# YarnControl_Connect_v1_0.net
KiCad netlist of a schematic drawn in Altium Designer
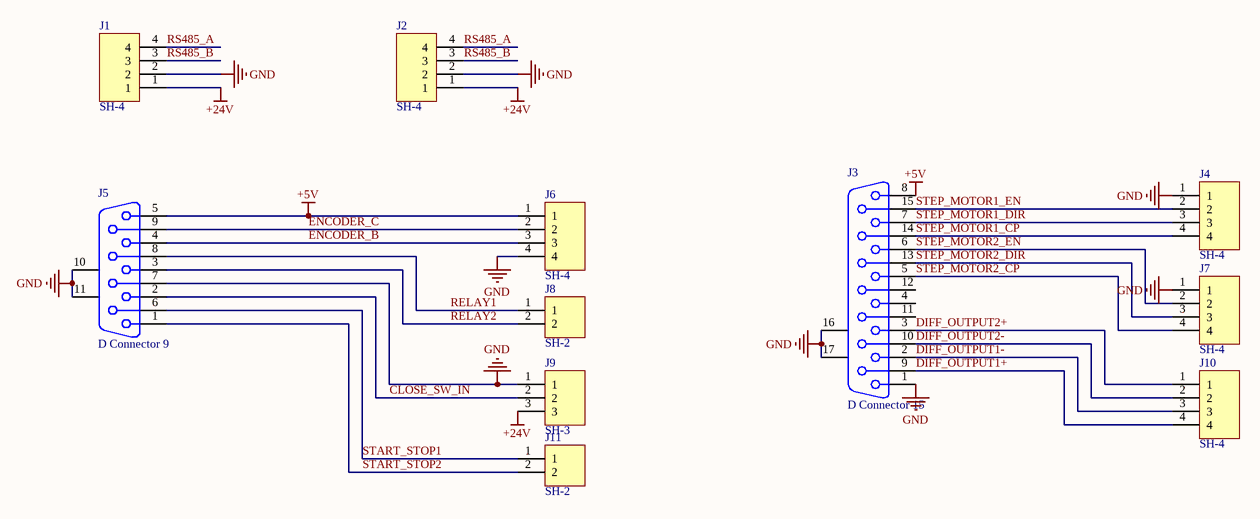
[diagram p0: YarnControl_Connect_v1.0.SchDoc]

(export (version "E")
  (design (tool "Eeschema 10.0.6"))
  (components
    (comp (ref "J1") (value "SH-4") (footprint "PWR") (libsource (lib "") (part "SH-4_1")))
    (comp (ref "J2") (value "SH-4") (footprint "PWR") (libsource (lib "") (part "SH-4_1")))
    (comp (ref "J3")
      (value "D Connector 15")
      (footprint "DSUB1.385-2H15")
      (description "Receptacle Assembly, 15 Position, Right Angle")
      (fields (field (name "PUBLISHER") "Altium Limited"))
      (libsource (lib "Miscellaneous Connectors") (part "D Connector 15"))
    )
    (comp (ref "J4") (value "SH-4") (footprint "PWR") (libsource (lib "Connector") (part "SH-4")))
    (comp (ref "J5")
      (value "D Connector 9")
      (footprint "DSUB1.385-2H9")
      (description "Receptacle Assembly, 9 Position, Right Angle")
      (fields (field (name "PUBLISHER") "Altium Limited"))
      (libsource (lib "Miscellaneous Connectors") (part "D Connector 9"))
    )
    (comp (ref "J6") (value "SH-4") (footprint "PWR") (libsource (lib "Connector") (part "SH-4")))
    (comp (ref "J7") (value "SH-4") (footprint "PWR") (libsource (lib "Connector") (part "SH-4")))
    (comp (ref "J8") (value "SH-2") (footprint "J508-2(1)") (libsource (lib "Connector") (part "SH-2")))
    (comp (ref "J9") (value "SH-3") (footprint "J508-3") (libsource (lib "Connector") (part "SH-3")))
    (comp (ref "J10") (value "SH-4") (footprint "PWR") (libsource (lib "Connector") (part "SH-4")))
    (comp (ref "J11") (value "SH-2") (footprint "J508-2(1)") (libsource (lib "Connector") (part "SH-2")))
  )
  (nets
    (net (code "1") (name "+5V") (class "Default")
      (node (ref "J3") (pin "8") (pinfunction "8_8") (pintype "passive"))
      (node (ref "J5") (pin "5") (pinfunction "5_5") (pintype "passive"))
      (node (ref "J6") (pin "1") (pinfunction "1_1") (pintype "passive"))
    )
    (net (code "2") (name "+24V") (class "Default")
      (node (ref "J1") (pin "1") (pinfunction "1_1") (pintype "passive"))
      (node (ref "J2") (pin "1") (pinfunction "1_1") (pintype "passive"))
      (node (ref "J9") (pin "3") (pinfunction "3_3") (pintype "passive"))
    )
    (net (code "3") (name "/CLOSE_SW_IN") (class "Default")
      (node (ref "J5") (pin "2") (pinfunction "2_2") (pintype "passive"))
      (node (ref "J9") (pin "2") (pinfunction "2_2") (pintype "passive"))
    )
    (net (code "4") (name "/DIFF_OUTPUT1+") (class "Default")
      (node (ref "J10") (pin "4") (pinfunction "4_4") (pintype "passive"))
      (node (ref "J3") (pin "9") (pinfunction "9_9") (pintype "passive"))
    )
    (net (code "5") (name "/DIFF_OUTPUT1-") (class "Default")
      (node (ref "J10") (pin "3") (pinfunction "3_3") (pintype "passive"))
      (node (ref "J3") (pin "2") (pinfunction "2_2") (pintype "passive"))
    )
    (net (code "6") (name "/DIFF_OUTPUT2+") (class "Default")
      (node (ref "J10") (pin "1") (pinfunction "1_1") (pintype "passive"))
      (node (ref "J3") (pin "3") (pinfunction "3_3") (pintype "passive"))
    )
    (net (code "7") (name "/DIFF_OUTPUT2-") (class "Default")
      (node (ref "J10") (pin "2") (pinfunction "2_2") (pintype "passive"))
      (node (ref "J3") (pin "10") (pinfunction "10_10") (pintype "passive"))
    )
    (net (code "8") (name "/ENCODER_B") (class "Default")
      (node (ref "J5") (pin "4") (pinfunction "4_4") (pintype "passive"))
      (node (ref "J6") (pin "3") (pinfunction "3_3") (pintype "passive"))
    )
    (net (code "9") (name "/ENCODER_C") (class "Default")
      (node (ref "J5") (pin "9") (pinfunction "9_9") (pintype "passive"))
      (node (ref "J6") (pin "2") (pinfunction "2_2") (pintype "passive"))
    )
    (net (code "10") (name "/RELAY1") (class "Default")
      (node (ref "J5") (pin "8") (pinfunction "8_8") (pintype "passive"))
      (node (ref "J8") (pin "1") (pinfunction "1_1") (pintype "passive"))
    )
    (net (code "11") (name "/RELAY2") (class "Default")
      (node (ref "J5") (pin "3") (pinfunction "3_3") (pintype "passive"))
      (node (ref "J8") (pin "2") (pinfunction "2_2") (pintype "passive"))
    )
    (net (code "12") (name "/RS485_A") (class "Default")
      (node (ref "J1") (pin "4") (pinfunction "4_4") (pintype "passive"))
      (node (ref "J2") (pin "4") (pinfunction "4_4") (pintype "passive"))
    )
    (net (code "13") (name "/RS485_B") (class "Default")
      (node (ref "J1") (pin "3") (pinfunction "3_3") (pintype "passive"))
      (node (ref "J2") (pin "3") (pinfunction "3_3") (pintype "passive"))
    )
    (net (code "14") (name "/START_STOP1") (class "Default")
      (node (ref "J11") (pin "1") (pinfunction "1_1") (pintype "passive"))
      (node (ref "J5") (pin "6") (pinfunction "6_6") (pintype "passive"))
    )
    (net (code "15") (name "/START_STOP2") (class "Default")
      (node (ref "J11") (pin "2") (pinfunction "2_2") (pintype "passive"))
      (node (ref "J5") (pin "1") (pinfunction "1_1") (pintype "passive"))
    )
    (net (code "16") (name "/STEP_MOTOR1_CP") (class "Default")
      (node (ref "J3") (pin "14") (pinfunction "14_14") (pintype "passive"))
      (node (ref "J4") (pin "4") (pinfunction "4_4") (pintype "passive"))
    )
    (net (code "17") (name "/STEP_MOTOR1_DIR") (class "Default")
      (node (ref "J3") (pin "7") (pinfunction "7_7") (pintype "passive"))
      (node (ref "J4") (pin "3") (pinfunction "3_3") (pintype "passive"))
    )
    (net (code "18") (name "/STEP_MOTOR1_EN") (class "Default")
      (node (ref "J3") (pin "15") (pinfunction "15_15") (pintype "passive"))
      (node (ref "J4") (pin "2") (pinfunction "2_2") (pintype "passive"))
    )
    (net (code "19") (name "/STEP_MOTOR2_CP") (class "Default")
      (node (ref "J3") (pin "5") (pinfunction "5_5") (pintype "passive"))
      (node (ref "J7") (pin "4") (pinfunction "4_4") (pintype "passive"))
    )
    (net (code "20") (name "/STEP_MOTOR2_DIR") (class "Default")
      (node (ref "J3") (pin "13") (pinfunction "13_13") (pintype "passive"))
      (node (ref "J7") (pin "3") (pinfunction "3_3") (pintype "passive"))
    )
    (net (code "21") (name "/STEP_MOTOR2_EN") (class "Default")
      (node (ref "J3") (pin "6") (pinfunction "6_6") (pintype "passive"))
      (node (ref "J7") (pin "2") (pinfunction "2_2") (pintype "passive"))
    )
    (net (code "22") (name "GND") (class "Default")
      (node (ref "J1") (pin "2") (pinfunction "2_2") (pintype "passive"))
      (node (ref "J2") (pin "2") (pinfunction "2_2") (pintype "passive"))
      (node (ref "J3") (pin "1") (pinfunction "1_1") (pintype "passive"))
      (node (ref "J3") (pin "16") (pinfunction "MH1_16") (pintype "passive"))
      (node (ref "J3") (pin "17") (pinfunction "MH2_17") (pintype "passive"))
      (node (ref "J4") (pin "1") (pinfunction "1_1") (pintype "passive"))
      (node (ref "J5") (pin "10") (pinfunction "MH1_10") (pintype "passive"))
      (node (ref "J5") (pin "11") (pinfunction "MH2_11") (pintype "passive"))
      (node (ref "J5") (pin "7") (pinfunction "7_7") (pintype "passive"))
      (node (ref "J6") (pin "4") (pinfunction "4_4") (pintype "passive"))
      (node (ref "J7") (pin "1") (pinfunction "1_1") (pintype "passive"))
      (node (ref "J9") (pin "1") (pinfunction "1_1") (pintype "passive"))
    )
    (net (code "23") (name "unconnected-(J3-Pad4)") (class "Default")
      (node (ref "J3") (pin "4") (pinfunction "4_4") (pintype "passive"))
    )
    (net (code "24") (name "unconnected-(J3-Pad11)") (class "Default")
      (node (ref "J3") (pin "11") (pinfunction "11_11") (pintype "passive"))
    )
    (net (code "25") (name "unconnected-(J3-Pad12)") (class "Default")
      (node (ref "J3") (pin "12") (pinfunction "12_12") (pintype "passive"))
    )
  )
)
